# true-bypass-2_0.net
KiCad netlist of a schematic drawn in EAGLE
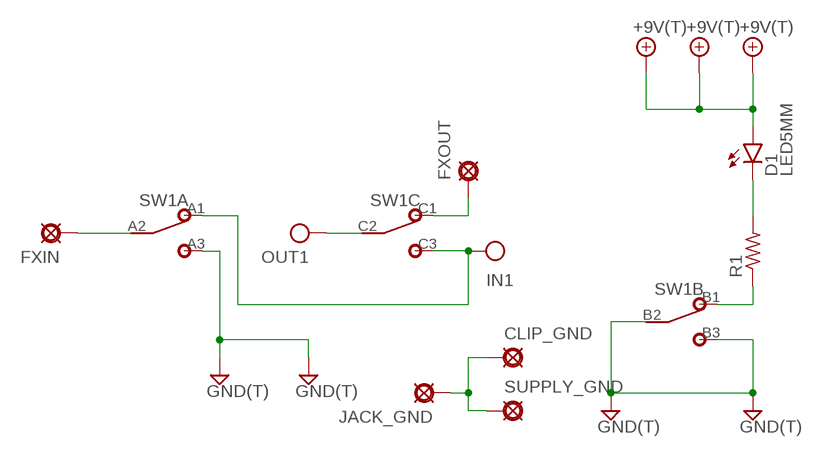
[diagram p0: schematic, sheet 1]

(export (version "E")
  (design (tool "Eeschema 10.0.6"))
  (components
    (comp (ref "+9V1")
      (value "+9V(T)")
      (footprint "eagle-import:SQUARE")
      (libsource (lib "eagle-import") (part "+9V(T)"))
    )
    (comp (ref "+9V2")
      (value "+9V(T)")
      (footprint "eagle-import:SQUARE")
      (libsource (lib "eagle-import") (part "+9V(T)"))
    )
    (comp (ref "+9V3")
      (value "+9V(T)")
      (footprint "eagle-import:SQUARE")
      (libsource (lib "eagle-import") (part "+9V(T)"))
    )
    (comp (ref "CLIP_GND")
      (value "PAD")
      (footprint "eagle-import:SQUARE")
      (libsource (lib "eagle-import") (part "PAD"))
    )
    (comp (ref "D1")
      (value "LED5MM")
      (footprint "eagle-import:LED5MM")
      (libsource (lib "eagle-import") (part "LED5MM"))
    )
    (comp (ref "FXIN")
      (value "PAD")
      (footprint "eagle-import:SQUARE")
      (libsource (lib "eagle-import") (part "PAD"))
    )
    (comp (ref "FXOUT")
      (value "PAD")
      (footprint "eagle-import:SQUARE")
      (libsource (lib "eagle-import") (part "PAD"))
    )
    (comp (ref "GND1")
      (value "GND(T)")
      (footprint "eagle-import:SQUARE")
      (libsource (lib "eagle-import") (part "GND(T)"))
    )
    (comp (ref "GND3")
      (value "GND(T)")
      (footprint "eagle-import:SQUARE")
      (libsource (lib "eagle-import") (part "GND(T)"))
    )
    (comp (ref "GND4")
      (value "GND(T)")
      (footprint "eagle-import:SQUARE")
      (libsource (lib "eagle-import") (part "GND(T)"))
    )
    (comp (ref "GND5")
      (value "GND(T)")
      (footprint "eagle-import:SQUARE")
      (libsource (lib "eagle-import") (part "GND(T)"))
    )
    (comp (ref "IN1")
      (value "IN(T)")
      (footprint "eagle-import:SQUARE")
      (libsource (lib "eagle-import") (part "IN(T)"))
    )
    (comp (ref "JACK_GND")
      (value "PAD")
      (footprint "eagle-import:SQUARE")
      (libsource (lib "eagle-import") (part "PAD"))
    )
    (comp (ref "OUT1")
      (value "OUT(T)")
      (footprint "eagle-import:SQUARE")
      (libsource (lib "eagle-import") (part "OUT(T)"))
    )
    (comp (ref "R1")
      (value "6MM.3")
      (footprint "eagle-import:R0207_3")
      (libsource (lib "eagle-import") (part "6MM.3"))
    )
    (comp (ref "SUPPLY_GND")
      (value "PAD")
      (footprint "eagle-import:SQUARE")
      (libsource (lib "eagle-import") (part "PAD"))
    )
    (comp (ref "SW1")
      (value "3PDTBLUE")
      (footprint "eagle-import:CHINABLUE")
      (libsource (lib "eagle-import") (part "3PDTBLUE"))
    )
  )
  (nets
    (net (code "1") (name "+9V(T)") (class "Default")
      (node (ref "+9V1") (pin "1") (pinfunction "+9V_1") (pintype "power_in"))
      (node (ref "+9V2") (pin "1") (pinfunction "+9V_1") (pintype "power_in"))
      (node (ref "+9V3") (pin "1") (pinfunction "+9V_1") (pintype "power_in"))
      (node (ref "D1") (pin "A") (pinfunction "A_A") (pintype "passive"))
    )
    (net (code "2") (name "GND(T)") (class "Default")
      (node (ref "GND1") (pin "1") (pinfunction "GND_1") (pintype "power_in"))
      (node (ref "GND3") (pin "1") (pinfunction "GND_1") (pintype "power_in"))
      (node (ref "GND4") (pin "1") (pinfunction "GND_1") (pintype "power_in"))
      (node (ref "GND5") (pin "1") (pinfunction "GND_1") (pintype "power_in"))
      (node (ref "SW1") (pin "A3") (pinfunction "3_A3") (pintype "passive"))
      (node (ref "SW1") (pin "B2") (pinfunction "2_B2") (pintype "passive"))
      (node (ref "SW1") (pin "B3") (pinfunction "3_B3") (pintype "passive"))
    )
    (net (code "3") (name "IN(T)") (class "Default")
      (node (ref "IN1") (pin "1") (pinfunction "IN_1") (pintype "power_in"))
      (node (ref "SW1") (pin "A1") (pinfunction "1_A1") (pintype "passive"))
      (node (ref "SW1") (pin "C3") (pinfunction "3_C3") (pintype "passive"))
    )
    (net (code "4") (name "Net-(CLIP_GND-PAD)") (class "Default")
      (node (ref "CLIP_GND") (pin "1") (pinfunction "PAD_1") (pintype "passive"))
      (node (ref "JACK_GND") (pin "1") (pinfunction "PAD_1") (pintype "passive"))
      (node (ref "SUPPLY_GND") (pin "1") (pinfunction "PAD_1") (pintype "passive"))
    )
    (net (code "5") (name "Net-(D1-C)") (class "Default")
      (node (ref "D1") (pin "K") (pinfunction "C_K") (pintype "passive"))
      (node (ref "R1") (pin "2") (pinfunction "2_2") (pintype "passive"))
    )
    (net (code "6") (name "Net-(FXIN-PAD)") (class "Default")
      (node (ref "FXIN") (pin "1") (pinfunction "PAD_1") (pintype "passive"))
      (node (ref "SW1") (pin "A2") (pinfunction "2_A2") (pintype "passive"))
    )
    (net (code "7") (name "Net-(FXOUT-PAD)") (class "Default")
      (node (ref "FXOUT") (pin "1") (pinfunction "PAD_1") (pintype "passive"))
      (node (ref "SW1") (pin "C1") (pinfunction "1_C1") (pintype "passive"))
    )
    (net (code "8") (name "Net-(SW1B-1)") (class "Default")
      (node (ref "R1") (pin "1") (pinfunction "1_1") (pintype "passive"))
      (node (ref "SW1") (pin "B1") (pinfunction "1_B1") (pintype "passive"))
    )
    (net (code "9") (name "OUT(T)") (class "Default")
      (node (ref "OUT1") (pin "1") (pinfunction "OUT_1") (pintype "power_in"))
      (node (ref "SW1") (pin "C2") (pinfunction "2_C2") (pintype "passive"))
    )
  )
)
